# IDP4.net
KiCad netlist of a schematic drawn in EAGLE
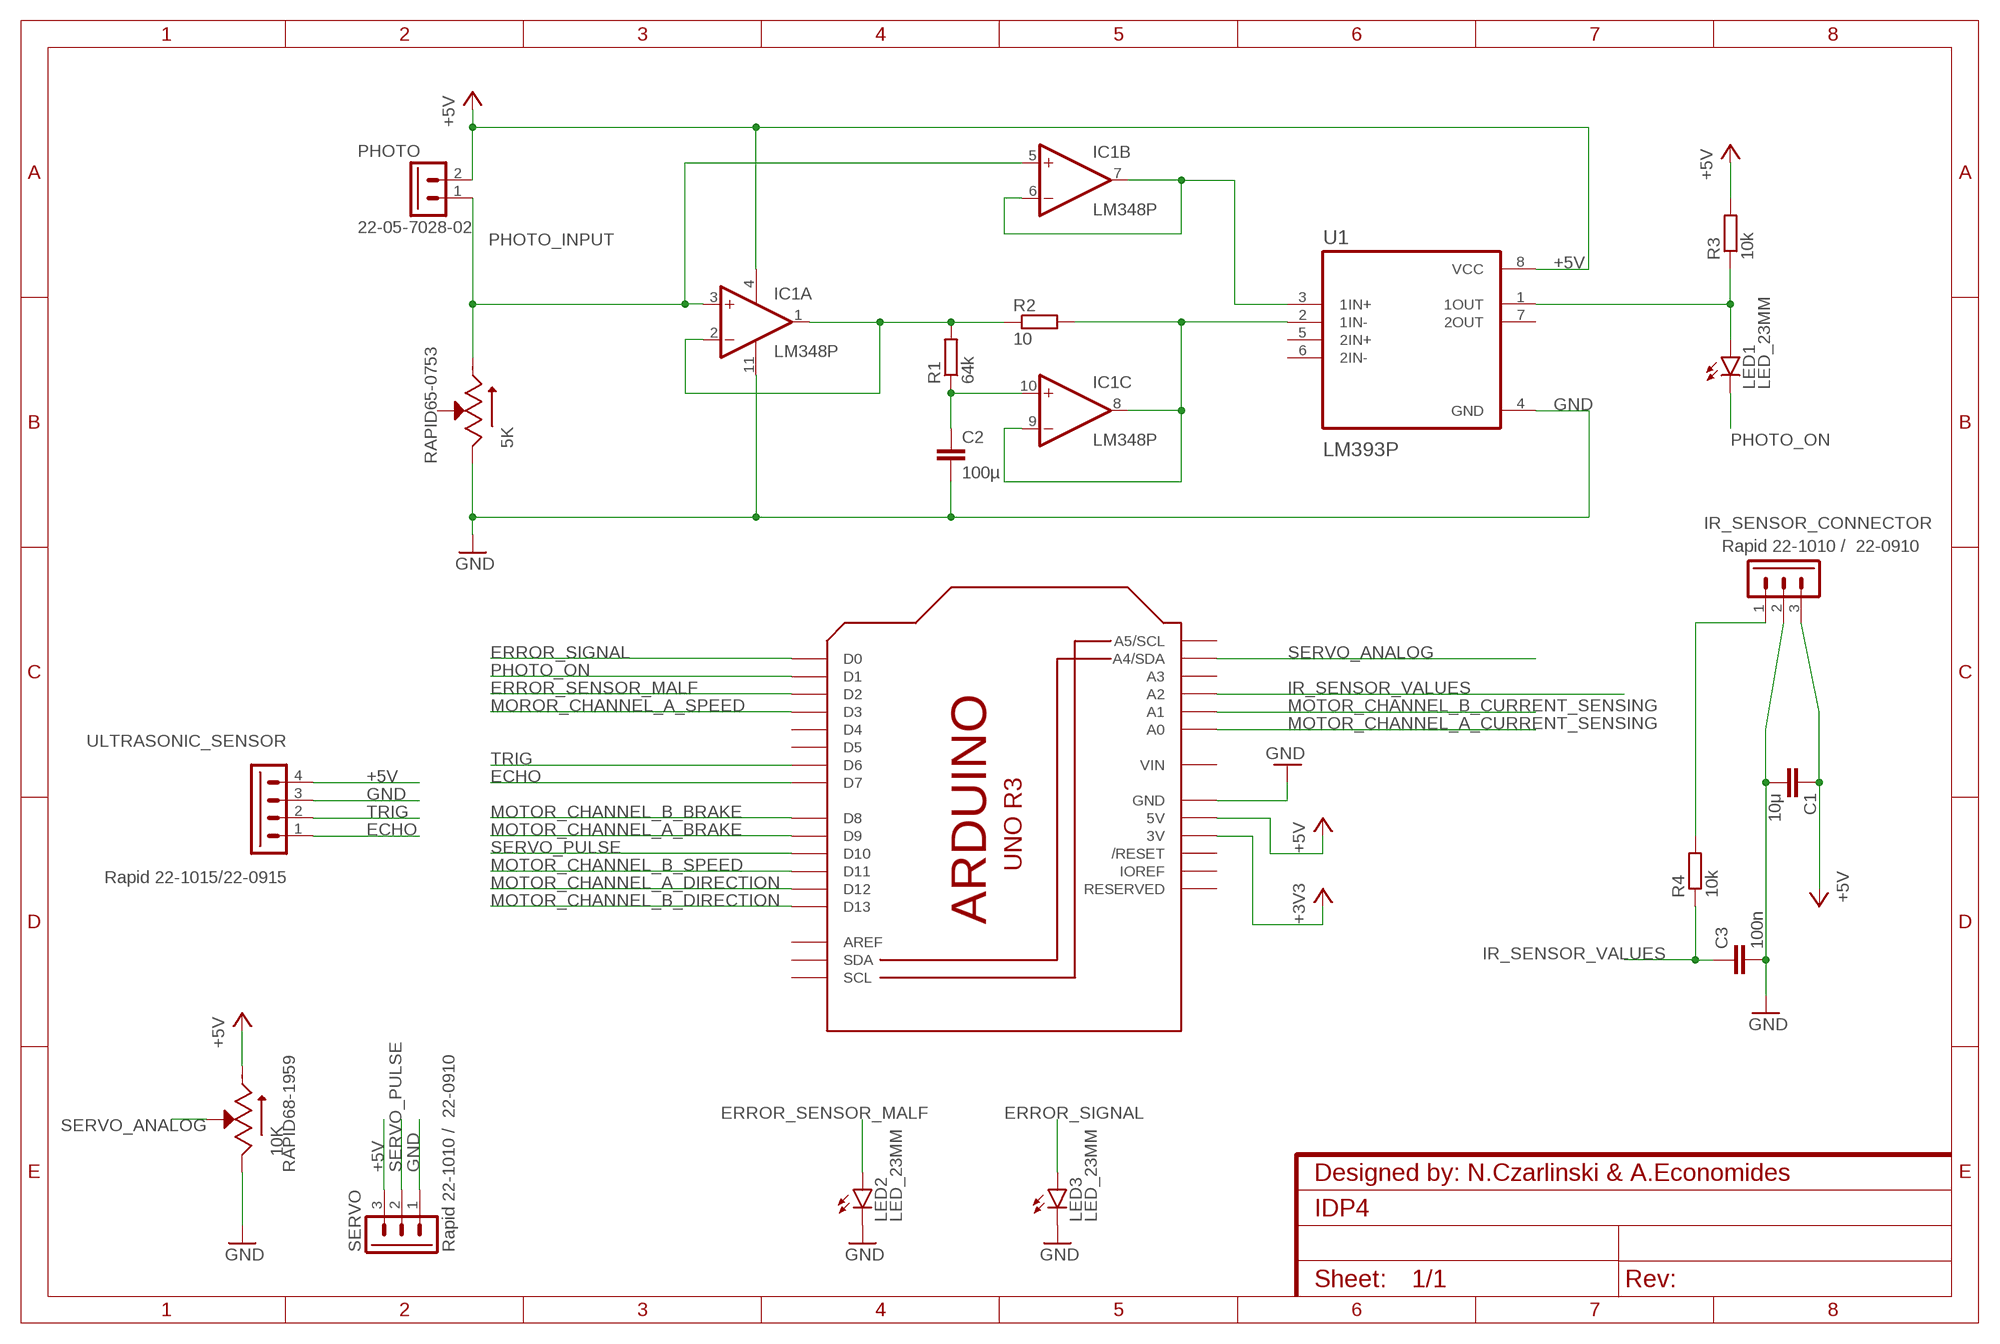
[diagram p0: schematic, sheet 1]

(export (version "E")
  (design (tool "Eeschema 10.0.6"))
  (components
    (comp (ref "C1")
      (value "10μ")
      (footprint "eagle-import:C025-024X044")
      (libsource (lib "eagle-import") (part "C-EU025-024X044"))
    )
    (comp (ref "C2")
      (value "100µ")
      (footprint "eagle-import:C025-024X044")
      (libsource (lib "eagle-import") (part "C-EU025-024X044"))
    )
    (comp (ref "C3")
      (value "100n")
      (footprint "eagle-import:C025-024X044")
      (libsource (lib "eagle-import") (part "C-EU025-024X044"))
    )
    (comp (ref "IC1")
      (value "LM348P")
      (footprint "eagle-import:DIL14")
      (libsource (lib "eagle-import") (part "LM348P"))
    )
    (comp (ref "IR_SENSOR_CONNECTOR")
      (value "Rapid 22-1010 / 22-0910")
      (footprint "eagle-import:7395-03")
      (fields (field (name "MF") "MOLEX"))
      (libsource (lib "eagle-import") (part "22-?-0305-7038"))
    )
    (comp (ref "LED1")
      (value "LED_23MM")
      (footprint "eagle-import:LED3MM")
      (libsource (lib "eagle-import") (part "LED_23MM"))
    )
    (comp (ref "LED2")
      (value "LED_23MM")
      (footprint "eagle-import:LED3MM")
      (libsource (lib "eagle-import") (part "LED_23MM"))
    )
    (comp (ref "LED3")
      (value "LED_23MM")
      (footprint "eagle-import:LED3MM")
      (libsource (lib "eagle-import") (part "LED_23MM"))
    )
    (comp (ref "M1")
      (value "IDP_PROTOBOARD")
      (footprint "eagle-import:IDP_PROTO")
      (libsource (lib "eagle-import") (part "IDP_PROTOBOARD"))
    )
    (comp (ref "PHOTO")
      (value "22-05-7028-02")
      (footprint "eagle-import:7395-02")
      (fields (field (name "MF") "MOLEX"))
      (libsource (lib "eagle-import") (part "22-?-0205-7028"))
    )
    (comp (ref "R1")
      (value "64k")
      (footprint "eagle-import:0204V")
      (libsource (lib "eagle-import") (part "R-EU_0204/2V"))
    )
    (comp (ref "R2")
      (value "10")
      (footprint "eagle-import:0204V")
      (libsource (lib "eagle-import") (part "R-EU_0204/2V"))
    )
    (comp (ref "R3")
      (value "10k")
      (footprint "eagle-import:0204V")
      (libsource (lib "eagle-import") (part "R-EU_0204/2V"))
    )
    (comp (ref "R4")
      (value "10k")
      (footprint "eagle-import:0204_7")
      (libsource (lib "eagle-import") (part "R-EU_0204/7"))
    )
    (comp (ref "RAPID65-0753")
      (value "5K")
      (footprint "eagle-import:TRIM_3296W-1-250")
      (fields (field (name "MF") "Bourns") (field (name "MP") "3296W-1-250"))
      (libsource (lib "eagle-import") (part "POT"))
    )
    (comp (ref "RAPID68-1959")
      (value "10K")
      (footprint "eagle-import:TRIM_3296W-1-250")
      (fields (field (name "MF") "Bourns") (field (name "MP") "3296W-1-250"))
      (libsource (lib "eagle-import") (part "POT"))
    )
    (comp (ref "SERVO")
      (value "Rapid 22-1010 / 22-0910")
      (footprint "eagle-import:7395-03")
      (fields (field (name "MF") "MOLEX"))
      (libsource (lib "eagle-import") (part "22-?-0305-7038"))
    )
    (comp (ref "U1")
      (value "LM393P")
      (footprint "eagle-import:DIP794W45P254L959H508Q8")
      (fields (field (name "MF") "Texas Instruments"))
      (libsource (lib "eagle-import") (part "LM393P"))
    )
    (comp (ref "ULTRASONIC_SENSOR")
      (value "Rapid 22-1015/22-0915")
      (footprint "eagle-import:7395-04")
      (fields (field (name "MF") "MOLEX"))
      (libsource (lib "eagle-import") (part "22-?-0405-7048"))
    )
  )
  (nets
    (net (code "1") (name "+3V3") (class "Default")
      (node (ref "M1") (pin "3V") (pinfunction "3V_3V") (pintype "power_in"))
    )
    (net (code "2") (name "+5V") (class "Default")
      (node (ref "C1") (pin "1") (pinfunction "1_1") (pintype "passive"))
      (node (ref "IC1") (pin "4") (pinfunction "V+_4") (pintype "power_in"))
      (node (ref "IR_SENSOR_CONNECTOR") (pin "3") (pinfunction "3_3") (pintype "passive"))
      (node (ref "M1") (pin "5V") (pinfunction "5V_5V") (pintype "power_in"))
      (node (ref "M1") (pin "5V@0") (pinfunction "5V_5V@0") (pintype "power_in"))
      (node (ref "M1") (pin "5V@1") (pinfunction "5V_5V@1") (pintype "power_in"))
      (node (ref "M1") (pin "5V@10") (pinfunction "5V_5V@10") (pintype "power_in"))
      (node (ref "M1") (pin "5V@11") (pinfunction "5V_5V@11") (pintype "power_in"))
      (node (ref "M1") (pin "5V@12") (pinfunction "5V_5V@12") (pintype "power_in"))
      (node (ref "M1") (pin "5V@13") (pinfunction "5V_5V@13") (pintype "power_in"))
      (node (ref "M1") (pin "5V@14") (pinfunction "5V_5V@14") (pintype "power_in"))
      (node (ref "M1") (pin "5V@15") (pinfunction "5V_5V@15") (pintype "power_in"))
      (node (ref "M1") (pin "5V@16") (pinfunction "5V_5V@16") (pintype "power_in"))
      (node (ref "M1") (pin "5V@17") (pinfunction "5V_5V@17") (pintype "power_in"))
      (node (ref "M1") (pin "5V@18") (pinfunction "5V_5V@18") (pintype "power_in"))
      (node (ref "M1") (pin "5V@19") (pinfunction "5V_5V@19") (pintype "power_in"))
      (node (ref "M1") (pin "5V@2") (pinfunction "5V_5V@2") (pintype "power_in"))
      (node (ref "M1") (pin "5V@20") (pinfunction "5V_5V@20") (pintype "power_in"))
      (node (ref "M1") (pin "5V@21") (pinfunction "5V_5V@21") (pintype "power_in"))
      (node (ref "M1") (pin "5V@22") (pinfunction "5V_5V@22") (pintype "power_in"))
      (node (ref "M1") (pin "5V@23") (pinfunction "5V_5V@23") (pintype "power_in"))
      (node (ref "M1") (pin "5V@24") (pinfunction "5V_5V@24") (pintype "power_in"))
      (node (ref "M1") (pin "5V@25") (pinfunction "5V_5V@25") (pintype "power_in"))
      (node (ref "M1") (pin "5V@26") (pinfunction "5V_5V@26") (pintype "power_in"))
      (node (ref "M1") (pin "5V@27") (pinfunction "5V_5V@27") (pintype "power_in"))
      (node (ref "M1") (pin "5V@28") (pinfunction "5V_5V@28") (pintype "power_in"))
      (node (ref "M1") (pin "5V@29") (pinfunction "5V_5V@29") (pintype "power_in"))
      (node (ref "M1") (pin "5V@3") (pinfunction "5V_5V@3") (pintype "power_in"))
      (node (ref "M1") (pin "5V@30") (pinfunction "5V_5V@30") (pintype "power_in"))
      (node (ref "M1") (pin "5V@31") (pinfunction "5V_5V@31") (pintype "power_in"))
      (node (ref "M1") (pin "5V@32") (pinfunction "5V_5V@32") (pintype "power_in"))
      (node (ref "M1") (pin "5V@33") (pinfunction "5V_5V@33") (pintype "power_in"))
      (node (ref "M1") (pin "5V@34") (pinfunction "5V_5V@34") (pintype "power_in"))
      (node (ref "M1") (pin "5V@35") (pinfunction "5V_5V@35") (pintype "power_in"))
      (node (ref "M1") (pin "5V@36") (pinfunction "5V_5V@36") (pintype "power_in"))
      (node (ref "M1") (pin "5V@37") (pinfunction "5V_5V@37") (pintype "power_in"))
      (node (ref "M1") (pin "5V@38") (pinfunction "5V_5V@38") (pintype "power_in"))
      (node (ref "M1") (pin "5V@39") (pinfunction "5V_5V@39") (pintype "power_in"))
      (node (ref "M1") (pin "5V@4") (pinfunction "5V_5V@4") (pintype "power_in"))
      (node (ref "M1") (pin "5V@40") (pinfunction "5V_5V@40") (pintype "power_in"))
      (node (ref "M1") (pin "5V@5") (pinfunction "5V_5V@5") (pintype "power_in"))
      (node (ref "M1") (pin "5V@6") (pinfunction "5V_5V@6") (pintype "power_in"))
      (node (ref "M1") (pin "5V@7") (pinfunction "5V_5V@7") (pintype "power_in"))
      (node (ref "M1") (pin "5V@8") (pinfunction "5V_5V@8") (pintype "power_in"))
      (node (ref "M1") (pin "5V@9") (pinfunction "5V_5V@9") (pintype "power_in"))
      (node (ref "PHOTO") (pin "2") (pinfunction "2_2") (pintype "passive"))
      (node (ref "R3") (pin "2") (pinfunction "2_2") (pintype "passive"))
      (node (ref "RAPID68-1959") (pin "3") (pinfunction "CW_3") (pintype "passive"))
      (node (ref "SERVO") (pin "3") (pinfunction "3_3") (pintype "passive"))
      (node (ref "U1") (pin "8") (pinfunction "VCC_8") (pintype "power_in"))
      (node (ref "ULTRASONIC_SENSOR") (pin "4") (pinfunction "4_4") (pintype "passive"))
    )
    (net (code "3") (name "/ECHO") (class "Default")
      (node (ref "M1") (pin "D7") (pinfunction "D7_D7") (pintype "bidirectional"))
      (node (ref "ULTRASONIC_SENSOR") (pin "1") (pinfunction "1_1") (pintype "passive"))
    )
    (net (code "4") (name "/ERROR_SENSOR_MALF") (class "Default")
      (node (ref "LED2") (pin "A") (pinfunction "A_A") (pintype "passive"))
      (node (ref "M1") (pin "D2") (pinfunction "D2_D2") (pintype "bidirectional"))
    )
    (net (code "5") (name "/ERROR_SIGNAL") (class "Default")
      (node (ref "LED3") (pin "A") (pinfunction "A_A") (pintype "passive"))
      (node (ref "M1") (pin "D0") (pinfunction "D0_D0") (pintype "bidirectional"))
    )
    (net (code "6") (name "/IR_SENSOR_VALUES") (class "Default")
      (node (ref "C3") (pin "1") (pinfunction "1_1") (pintype "passive"))
      (node (ref "M1") (pin "A2") (pinfunction "A2_A2") (pintype "bidirectional"))
      (node (ref "R4") (pin "1") (pinfunction "1_1") (pintype "passive"))
    )
    (net (code "7") (name "/MOROR_CHANNEL_A_SPEED") (class "Default")
      (node (ref "M1") (pin "D3") (pinfunction "D3_D3") (pintype "bidirectional"))
    )
    (net (code "8") (name "/MOTOR_CHANNEL_A_BRAKE") (class "Default")
      (node (ref "M1") (pin "D9") (pinfunction "D9_D9") (pintype "bidirectional"))
    )
    (net (code "9") (name "/MOTOR_CHANNEL_A_CURRENT_SENSING") (class "Default")
      (node (ref "M1") (pin "A0") (pinfunction "A0_A0") (pintype "bidirectional"))
    )
    (net (code "10") (name "/MOTOR_CHANNEL_A_DIRECTION") (class "Default")
      (node (ref "M1") (pin "D12") (pinfunction "D12_D12") (pintype "bidirectional"))
    )
    (net (code "11") (name "/MOTOR_CHANNEL_B_BRAKE") (class "Default")
      (node (ref "M1") (pin "D8") (pinfunction "D8_D8") (pintype "bidirectional"))
    )
    (net (code "12") (name "/MOTOR_CHANNEL_B_CURRENT_SENSING") (class "Default")
      (node (ref "M1") (pin "A1") (pinfunction "A1_A1") (pintype "bidirectional"))
    )
    (net (code "13") (name "/MOTOR_CHANNEL_B_DIRECTION") (class "Default")
      (node (ref "M1") (pin "D13") (pinfunction "D13_D13") (pintype "bidirectional"))
    )
    (net (code "14") (name "/MOTOR_CHANNEL_B_SPEED") (class "Default")
      (node (ref "M1") (pin "D11") (pinfunction "D11_D11") (pintype "bidirectional"))
    )
    (net (code "15") (name "/PHOTO_INPUT") (class "Default")
      (node (ref "IC1") (pin "3") (pinfunction "+IN_3") (pintype "input"))
      (node (ref "IC1") (pin "5") (pinfunction "+IN_5") (pintype "input"))
      (node (ref "PHOTO") (pin "1") (pinfunction "1_1") (pintype "passive"))
      (node (ref "RAPID65-0753") (pin "3") (pinfunction "CW_3") (pintype "passive"))
    )
    (net (code "16") (name "/PHOTO_ON") (class "Default")
      (node (ref "LED1") (pin "A") (pinfunction "A_A") (pintype "passive"))
      (node (ref "LED1") (pin "K") (pinfunction "C_K") (pintype "passive"))
      (node (ref "M1") (pin "D1") (pinfunction "D1_D1") (pintype "bidirectional"))
      (node (ref "R3") (pin "1") (pinfunction "1_1") (pintype "passive"))
      (node (ref "U1") (pin "1") (pinfunction "1OUT_1") (pintype "output"))
    )
    (net (code "17") (name "/SERVO_ANALOG") (class "Default")
      (node (ref "M1") (pin "A4") (pinfunction "A4/SDA_A4") (pintype "bidirectional"))
      (node (ref "RAPID68-1959") (pin "2") (pinfunction "WIPER_2") (pintype "passive"))
    )
    (net (code "18") (name "/SERVO_PULSE") (class "Default")
      (node (ref "M1") (pin "D10") (pinfunction "D10_D10") (pintype "bidirectional"))
      (node (ref "SERVO") (pin "2") (pinfunction "2_2") (pintype "passive"))
    )
    (net (code "19") (name "/TRIG") (class "Default")
      (node (ref "M1") (pin "D6") (pinfunction "D6_D6") (pintype "bidirectional"))
      (node (ref "ULTRASONIC_SENSOR") (pin "2") (pinfunction "2_2") (pintype "passive"))
    )
    (net (code "20") (name "GND") (class "Default")
      (node (ref "C1") (pin "2") (pinfunction "2_2") (pintype "passive"))
      (node (ref "C2") (pin "2") (pinfunction "2_2") (pintype "passive"))
      (node (ref "C3") (pin "2") (pinfunction "2_2") (pintype "passive"))
      (node (ref "IC1") (pin "11") (pinfunction "V-_11") (pintype "power_in"))
      (node (ref "IR_SENSOR_CONNECTOR") (pin "2") (pinfunction "2_2") (pintype "passive"))
      (node (ref "LED2") (pin "K") (pinfunction "C_K") (pintype "passive"))
      (node (ref "LED3") (pin "K") (pinfunction "C_K") (pintype "passive"))
      (node (ref "M1") (pin "GND") (pinfunction "GND_GND") (pintype "power_in"))
      (node (ref "M1") (pin "GND16") (pinfunction "GND_GND16") (pintype "power_in"))
      (node (ref "M1") (pin "GND17") (pinfunction "GND_GND17") (pintype "power_in"))
      (node (ref "M1") (pin "GND18") (pinfunction "GND_GND18") (pintype "power_in"))
      (node (ref "M1") (pin "GND19") (pinfunction "GND_GND19") (pintype "power_in"))
      (node (ref "M1") (pin "GND20") (pinfunction "GND_GND20") (pintype "power_in"))
      (node (ref "M1") (pin "GND21") (pinfunction "GND_GND21") (pintype "power_in"))
      (node (ref "M1") (pin "GND22") (pinfunction "GND_GND22") (pintype "power_in"))
      (node (ref "M1") (pin "GND23") (pinfunction "GND_GND23") (pintype "power_in"))
      (node (ref "M1") (pin "GND24") (pinfunction "GND_GND24") (pintype "power_in"))
      (node (ref "M1") (pin "GND25") (pinfunction "GND_GND25") (pintype "power_in"))
      (node (ref "M1") (pin "GND@1") (pinfunction "GND_GND@1") (pintype "power_in"))
      (node (ref "M1") (pin "GND@10") (pinfunction "GND_GND@10") (pintype "power_in"))
      (node (ref "M1") (pin "GND@11") (pinfunction "GND_GND@11") (pintype "power_in"))
      (node (ref "M1") (pin "GND@12") (pinfunction "GND_GND@12") (pintype "power_in"))
      (node (ref "M1") (pin "GND@13") (pinfunction "GND_GND@13") (pintype "power_in"))
      (node (ref "M1") (pin "GND@14") (pinfunction "GND_GND@14") (pintype "power_in"))
      (node (ref "M1") (pin "GND@15") (pinfunction "GND_GND@15") (pintype "power_in"))
      (node (ref "M1") (pin "GND@2") (pinfunction "GND_GND@2") (pintype "power_in"))
      (node (ref "M1") (pin "GND@26") (pinfunction "GND_GND@26") (pintype "power_in"))
      (node (ref "M1") (pin "GND@27") (pinfunction "GND_GND@27") (pintype "power_in"))
      (node (ref "M1") (pin "GND@28") (pinfunction "GND_GND@28") (pintype "power_in"))
      (node (ref "M1") (pin "GND@29") (pinfunction "GND_GND@29") (pintype "power_in"))
      (node (ref "M1") (pin "GND@3") (pinfunction "GND_GND@3") (pintype "power_in"))
      (node (ref "M1") (pin "GND@30") (pinfunction "GND_GND@30") (pintype "power_in"))
      (node (ref "M1") (pin "GND@31") (pinfunction "GND_GND@31") (pintype "power_in"))
      (node (ref "M1") (pin "GND@32") (pinfunction "GND_GND@32") (pintype "power_in"))
      (node (ref "M1") (pin "GND@33") (pinfunction "GND_GND@33") (pintype "power_in"))
      (node (ref "M1") (pin "GND@34") (pinfunction "GND_GND@34") (pintype "power_in"))
      (node (ref "M1") (pin "GND@35") (pinfunction "GND_GND@35") (pintype "power_in"))
      (node (ref "M1") (pin "GND@36") (pinfunction "GND_GND@36") (pintype "power_in"))
      (node (ref "M1") (pin "GND@37") (pinfunction "GND_GND@37") (pintype "power_in"))
      (node (ref "M1") (pin "GND@38") (pinfunction "GND_GND@38") (pintype "power_in"))
      (node (ref "M1") (pin "GND@39") (pinfunction "GND_GND@39") (pintype "power_in"))
      (node (ref "M1") (pin "GND@4") (pinfunction "GND_GND@4") (pintype "power_in"))
      (node (ref "M1") (pin "GND@40") (pinfunction "GND_GND@40") (pintype "power_in"))
      (node (ref "M1") (pin "GND@41") (pinfunction "GND_GND@41") (pintype "power_in"))
      (node (ref "M1") (pin "GND@42") (pinfunction "GND_GND@42") (pintype "power_in"))
      (node (ref "M1") (pin "GND@43") (pinfunction "GND_GND@43") (pintype "power_in"))
      (node (ref "M1") (pin "GND@44") (pinfunction "GND_GND@44") (pintype "power_in"))
      (node (ref "M1") (pin "GND@45") (pinfunction "GND_GND@45") (pintype "power_in"))
      (node (ref "M1") (pin "GND@46") (pinfunction "GND_GND@46") (pintype "power_in"))
      (node (ref "M1") (pin "GND@47") (pinfunction "GND_GND@47") (pintype "power_in"))
      (node (ref "M1") (pin "GND@48") (pinfunction "GND_GND@48") (pintype "power_in"))
      (node (ref "M1") (pin "GND@5") (pinfunction "GND_GND@5") (pintype "power_in"))
      (node (ref "M1") (pin "GND@6") (pinfunction "GND_GND@6") (pintype "power_in"))
      (node (ref "M1") (pin "GND@7") (pinfunction "GND_GND@7") (pintype "power_in"))
      (node (ref "M1") (pin "GND@8") (pinfunction "GND_GND@8") (pintype "power_in"))
      (node (ref "M1") (pin "GND@9") (pinfunction "GND_GND@9") (pintype "power_in"))
      (node (ref "RAPID65-0753") (pin "1") (pinfunction "CCW_1") (pintype "passive"))
      (node (ref "RAPID68-1959") (pin "1") (pinfunction "CCW_1") (pintype "passive"))
      (node (ref "SERVO") (pin "1") (pinfunction "1_1") (pintype "passive"))
      (node (ref "U1") (pin "4") (pinfunction "GND_4") (pintype "power_in"))
      (node (ref "ULTRASONIC_SENSOR") (pin "3") (pinfunction "3_3") (pintype "passive"))
    )
    (net (code "21") (name "Net-(IC1A--IN)") (class "Default")
      (node (ref "IC1") (pin "1") (pinfunction "OUT_1") (pintype "output"))
      (node (ref "IC1") (pin "2") (pinfunction "-IN_2") (pintype "input"))
      (node (ref "R1") (pin "2") (pinfunction "2_2") (pintype "passive"))
      (node (ref "R2") (pin "1") (pinfunction "1_1") (pintype "passive"))
    )
    (net (code "22") (name "Net-(IC1B--IN)") (class "Default")
      (node (ref "IC1") (pin "6") (pinfunction "-IN_6") (pintype "input"))
      (node (ref "IC1") (pin "7") (pinfunction "OUT_7") (pintype "output"))
      (node (ref "U1") (pin "3") (pinfunction "1IN+_3") (pintype "input"))
    )
    (net (code "23") (name "Net-(IC1C-+IN)") (class "Default")
      (node (ref "C2") (pin "1") (pinfunction "1_1") (pintype "passive"))
      (node (ref "IC1") (pin "10") (pinfunction "+IN_10") (pintype "input"))
      (node (ref "R1") (pin "1") (pinfunction "1_1") (pintype "passive"))
    )
    (net (code "24") (name "Net-(IC1C--IN)") (class "Default")
      (node (ref "IC1") (pin "8") (pinfunction "OUT_8") (pintype "output"))
      (node (ref "IC1") (pin "9") (pinfunction "-IN_9") (pintype "input"))
      (node (ref "R2") (pin "2") (pinfunction "2_2") (pintype "passive"))
      (node (ref "U1") (pin "2") (pinfunction "1IN-_2") (pintype "input"))
    )
    (net (code "25") (name "Net-(IR_SENSOR_CONNECTOR-Pad1)") (class "Default")
      (node (ref "IR_SENSOR_CONNECTOR") (pin "1") (pinfunction "1_1") (pintype "passive"))
      (node (ref "R4") (pin "2") (pinfunction "2_2") (pintype "passive"))
    )
    (net (code "26") (name "unconnected-(M1-A5{slash}SCL-PadA5)") (class "Default")
      (node (ref "M1") (pin "A5") (pinfunction "A5/SCL_A5") (pintype "bidirectional"))
    )
    (net (code "27") (name "unconnected-(M1-PadA3)") (class "Default")
      (node (ref "M1") (pin "A3") (pinfunction "A3_A3") (pintype "bidirectional"))
    )
    (net (code "28") (name "unconnected-(M1-PadAREF)") (class "Default")
      (node (ref "M1") (pin "AREF") (pinfunction "AREF_AREF") (pintype "bidirectional"))
    )
    (net (code "29") (name "unconnected-(M1-PadD4)") (class "Default")
      (node (ref "M1") (pin "D4") (pinfunction "D4_D4") (pintype "bidirectional"))
    )
    (net (code "30") (name "unconnected-(M1-PadD5)") (class "Default")
      (node (ref "M1") (pin "D5") (pinfunction "D5_D5") (pintype "bidirectional"))
    )
    (net (code "31") (name "unconnected-(M1-PadIOREF)") (class "Default")
      (node (ref "M1") (pin "IOREF") (pinfunction "IOREF_IOREF") (pintype "output"))
    )
    (net (code "32") (name "unconnected-(M1-PadRESERVED)") (class "Default")
      (node (ref "M1") (pin "RESERVED") (pinfunction "RESERVED_RESERVED") (pintype "no_connect"))
    )
    (net (code "33") (name "unconnected-(M1-PadSCL)") (class "Default")
      (node (ref "M1") (pin "SCL") (pinfunction "SCL_SCL") (pintype "bidirectional"))
    )
    (net (code "34") (name "unconnected-(M1-PadSDA)") (class "Default")
      (node (ref "M1") (pin "SDA") (pinfunction "SDA_SDA") (pintype "bidirectional"))
    )
    (net (code "35") (name "unconnected-(M1-PadVIN)") (class "Default")
      (node (ref "M1") (pin "VIN") (pinfunction "VIN_VIN") (pintype "no_connect"))
    )
    (net (code "36") (name "unconnected-(M1-{slash}RESET-PadRESET)") (class "Default")
      (node (ref "M1") (pin "RESET") (pinfunction "/RESET_RESET") (pintype "bidirectional"))
    )
    (net (code "37") (name "unconnected-(RAPID65-0753-WIPER-Pad2)") (class "Default")
      (node (ref "RAPID65-0753") (pin "2") (pinfunction "WIPER_2") (pintype "passive"))
    )
    (net (code "38") (name "unconnected-(U1-2IN+-Pad5)") (class "Default")
      (node (ref "U1") (pin "5") (pinfunction "2IN+_5") (pintype "input"))
    )
    (net (code "39") (name "unconnected-(U1-2IN--Pad6)") (class "Default")
      (node (ref "U1") (pin "6") (pinfunction "2IN-_6") (pintype "input"))
    )
    (net (code "40") (name "unconnected-(U1-2OUT-Pad7)") (class "Default")
      (node (ref "U1") (pin "7") (pinfunction "2OUT_7") (pintype "output"))
    )
  )
)
